# Laser_Tec_Control.net
KiCad netlist of a schematic drawn in Altium Designer
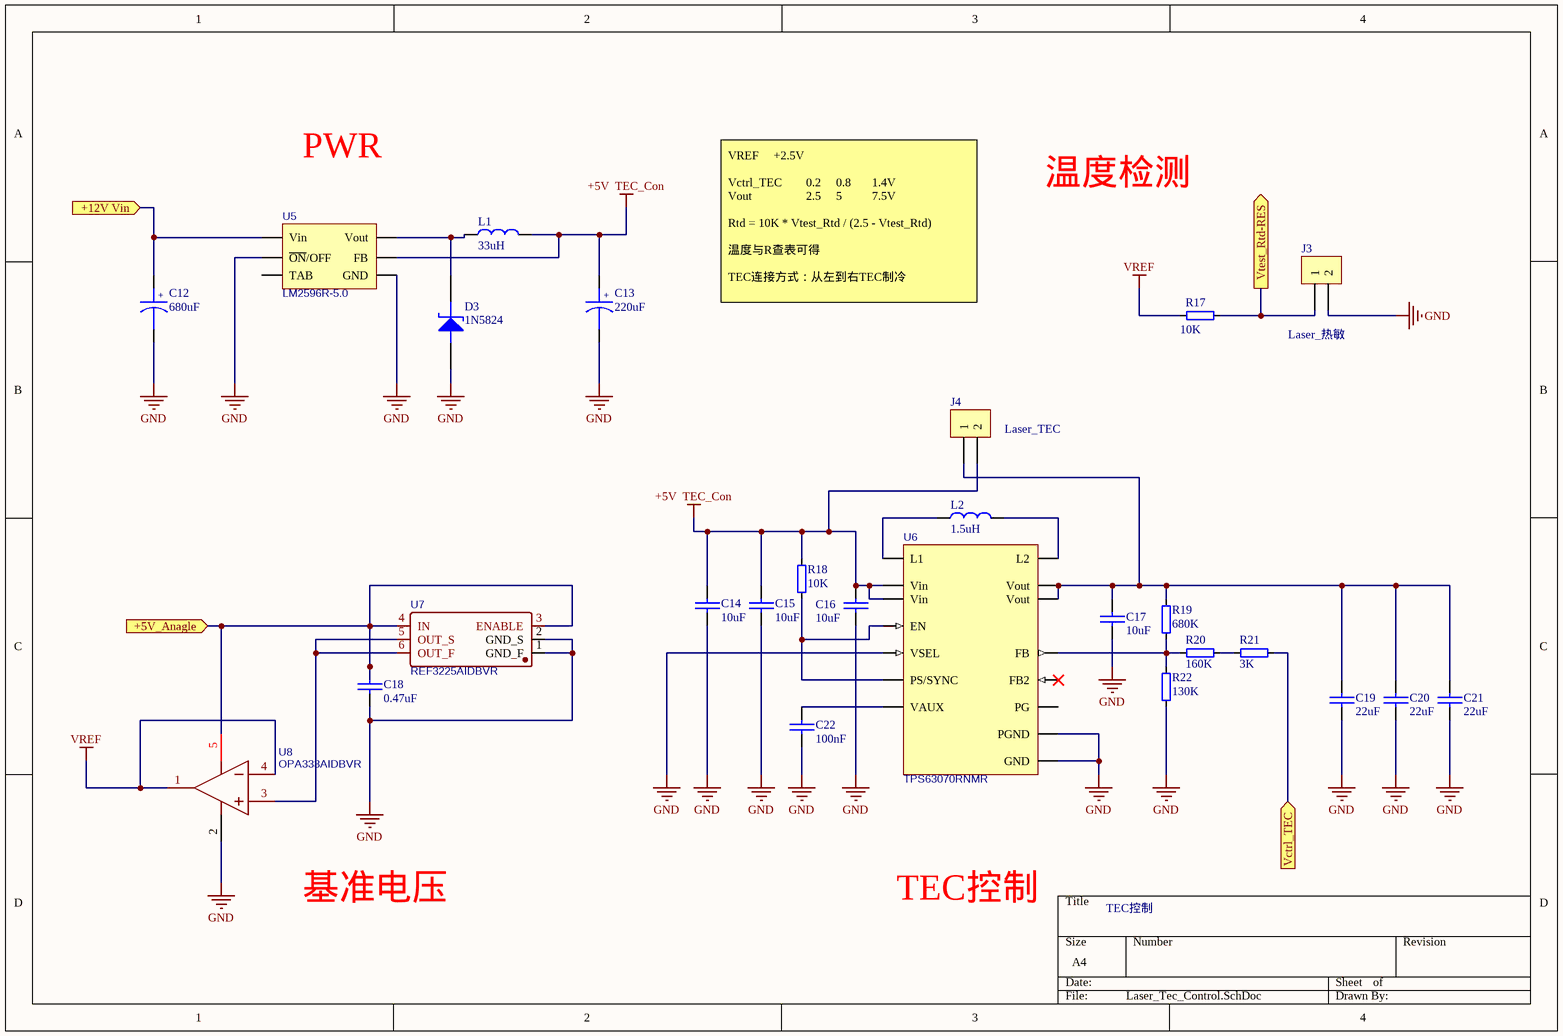
[diagram p0: Laser_Tec_Control.SchDoc]

(export (version "E")
  (design (tool "Eeschema 10.0.6"))
  (components
    (comp (ref "C12")
      (value "680uF")
      (footprint "CAP-TH_BD8.0-P3.50-D0.6-FD")
      (description "Capacitor")
      (libsource (lib "Laser Controller") (part "电解电容1"))
    )
    (comp (ref "C13")
      (value "220uF")
      (footprint "CAP-TH_BD8.0-P3.50-D0.6-FD")
      (description "Capacitor")
      (libsource (lib "Laser Controller") (part "电解电容1"))
    )
    (comp (ref "C14")
      (value "10uF")
      (footprint "C 0603_M")
      (description "Capacitor 0805")
      (libsource (lib "Laser Controller") (part "普通电容"))
    )
    (comp (ref "C15")
      (value "10uF")
      (footprint "C 0603_M")
      (description "Capacitor,0805")
      (libsource (lib "Laser Controller") (part "普通电容"))
    )
    (comp (ref "C16")
      (value "10uF")
      (footprint "C 0603_M")
      (description "Capacitor,0603")
      (libsource (lib "Laser Controller") (part "普通电容"))
    )
    (comp (ref "C17")
      (value "10uF")
      (footprint "C 0603_M")
      (description "Capacitor,0603")
      (libsource (lib "Laser Controller") (part "普通电容"))
    )
    (comp (ref "C18")
      (value "0.47uF")
      (footprint "C 0603_M")
      (description "Capacitor")
      (libsource (lib "Laser Controller") (part "普通电容"))
    )
    (comp (ref "C19")
      (value "22uF")
      (footprint "C 0603_M")
      (description "Capacitor,0805")
      (libsource (lib "Laser Controller") (part "普通电容"))
    )
    (comp (ref "C20")
      (value "22uF")
      (footprint "C 0603_M")
      (description "Capacitor 0805")
      (libsource (lib "Laser Controller") (part "普通电容"))
    )
    (comp (ref "C21")
      (value "22uF")
      (footprint "C 0603_M")
      (description "Capacitor 0805")
      (libsource (lib "Laser Controller") (part "普通电容"))
    )
    (comp (ref "C22")
      (value "100nF")
      (footprint "C 0603_M")
      (description "Capacitor")
      (libsource (lib "Laser Controller") (part "普通电容"))
    )
    (comp (ref "D3")
      (value "1N5824")
      (footprint "SMA_L4.3-W2.6-LS5.0-RD")
      (description "Zener Diode")
      (libsource (lib "Laser Controller") (part "1N5824"))
    )
    (comp (ref "J3")
      (value "Laser_热敏")
      (footprint "KF128-5.08-2P")
      (description "jointbar")
      (libsource (lib "Laser Controller") (part "SIP2"))
    )
    (comp (ref "J4")
      (value "Laser_TEC")
      (footprint "KF128-5.08-2P")
      (description "jointbar")
      (libsource (lib "Laser Controller") (part "SIP2"))
    )
    (comp (ref "L1")
      (value "33uH")
      (footprint "L 0805")
      (description "电感")
      (libsource (lib "Laser Controller") (part "L1"))
    )
    (comp (ref "L2")
      (value "1.5uH")
      (footprint "L 0805")
      (description "电感")
      (libsource (lib "Laser Controller") (part "L1"))
    )
    (comp (ref "R17") (value "10K") (footprint "0603R") (libsource (lib "Laser Controller") (part "普通电阻")))
    (comp (ref "R18") (value "10K") (footprint "0603R") (libsource (lib "Laser Controller") (part "普通电阻")))
    (comp (ref "R19") (value "680K") (footprint "0603R") (libsource (lib "Laser Controller") (part "普通电阻")))
    (comp (ref "R20") (value "160K") (footprint "0603R") (libsource (lib "Laser Controller") (part "普通电阻")))
    (comp (ref "R21") (value "3K") (footprint "0603R") (libsource (lib "Laser Controller") (part "普通电阻")))
    (comp (ref "R22") (value "130K") (footprint "0603R") (libsource (lib "Laser Controller") (part "普通电阻")))
    (comp (ref "U5")
      (value "LM2596R-5.0")
      (footprint "TO-263-5_L10.2-W8.6-P1.70-LS14.4-TL")
      (fields (field (name "BOM_SUPPLIER PART") "C77782"))
      (libsource (lib "Laser Controller") (part "LM2596R-5.0"))
    )
    (comp (ref "U6")
      (value "TPS63070RNMR")
      (footprint "VQFN-HR-15_L3.0-W2.5-P0.50-BL_TPS63070RNMR")
      (fields (field (name "BOM_SUPPLIER PART") "C109322"))
      (libsource (lib "Laser Controller") (part "TPS63070RNMR"))
    )
    (comp (ref "U7")
      (value "REF3225AIDBVR")
      (footprint "SOT-23-6_L2.9-W1.6-P0.95-LS2.8-BL")
      (fields (field (name "BOM_SUPPLIER PART") "C40852"))
      (libsource (lib "Laser Controller") (part "REF3225AIDBVR"))
    )
    (comp (ref "U8")
      (value "OPA333AIDBVR")
      (footprint "SOT-23-5_L3.0-W1.7-P0.95-LS2.8-BR")
      (fields (field (name "BOM_SUPPLIER PART") "C30878") (field (name "CONTRIBUTOR") "LCSC"))
      (libsource (lib "Laser Controller") (part "OPA333AIDBVR"))
    )
  )
  (nets
    (net (code "1") (name "+5V  TEC_Con") (class "Default")
      (node (ref "C13") (pin "1") (pinfunction "1_1") (pintype "passive"))
      (node (ref "C14") (pin "1") (pinfunction "1_1") (pintype "passive"))
      (node (ref "C15") (pin "1") (pinfunction "1_1") (pintype "passive"))
      (node (ref "C16") (pin "1") (pinfunction "1_1") (pintype "passive"))
      (node (ref "J4") (pin "2") (pinfunction "2_2") (pintype "passive"))
      (node (ref "L1") (pin "1") (pinfunction "1_1") (pintype "passive"))
      (node (ref "R18") (pin "2") (pinfunction "2_2") (pintype "passive"))
      (node (ref "U5") (pin "4") (pinfunction "FB_4") (pintype "passive"))
      (node (ref "U6") (pin "12") (pinfunction "Vin_12") (pintype "passive"))
      (node (ref "U6") (pin "13") (pinfunction "Vin_13") (pintype "passive"))
    )
    (net (code "2") (name "/+5V_Anagle") (class "Default")
      (node (ref "C18") (pin "1") (pinfunction "1_1") (pintype "passive"))
      (node (ref "U7") (pin "3") (pinfunction "ENABLE_3") (pintype "passive"))
      (node (ref "U7") (pin "4") (pinfunction "IN_4") (pintype "passive"))
      (node (ref "U8") (pin "5") (pinfunction "V+_5") (pintype "passive"))
    )
    (net (code "3") (name "/+12V Vin") (class "Default")
      (node (ref "C12") (pin "1") (pinfunction "1_1") (pintype "passive"))
      (node (ref "U5") (pin "1") (pinfunction "Vin_1") (pintype "passive"))
    )
    (net (code "4") (name "/Vctrl_TEC") (class "Default")
      (node (ref "R21") (pin "1") (pinfunction "1_1") (pintype "passive"))
    )
    (net (code "5") (name "/Vtest_Rtd-RES") (class "Default")
      (node (ref "J3") (pin "1") (pinfunction "1_1") (pintype "passive"))
      (node (ref "R17") (pin "2") (pinfunction "2_2") (pintype "passive"))
    )
    (net (code "6") (name "GND") (class "Default")
      (node (ref "C12") (pin "2") (pinfunction "2_2") (pintype "passive"))
      (node (ref "C13") (pin "2") (pinfunction "2_2") (pintype "passive"))
      (node (ref "C14") (pin "2") (pinfunction "2_2") (pintype "passive"))
      (node (ref "C15") (pin "2") (pinfunction "2_2") (pintype "passive"))
      (node (ref "C16") (pin "2") (pinfunction "2_2") (pintype "passive"))
      (node (ref "C17") (pin "2") (pinfunction "2_2") (pintype "passive"))
      (node (ref "C18") (pin "2") (pinfunction "2_2") (pintype "passive"))
      (node (ref "C19") (pin "2") (pinfunction "2_2") (pintype "passive"))
      (node (ref "C20") (pin "2") (pinfunction "2_2") (pintype "passive"))
      (node (ref "C21") (pin "2") (pinfunction "2_2") (pintype "passive"))
      (node (ref "C22") (pin "2") (pinfunction "2_2") (pintype "passive"))
      (node (ref "D3") (pin "1") (pinfunction "A_1") (pintype "passive"))
      (node (ref "J3") (pin "2") (pinfunction "2_2") (pintype "passive"))
      (node (ref "R22") (pin "1") (pinfunction "1_1") (pintype "passive"))
      (node (ref "U5") (pin "3") (pinfunction "GND_3") (pintype "passive"))
      (node (ref "U5") (pin "5") (pinfunction "~{ON}/OFF_5") (pintype "passive"))
      (node (ref "U6") (pin "10") (pinfunction "PGND_10") (pintype "passive"))
      (node (ref "U6") (pin "15") (pinfunction "VSEL_15") (pintype "input"))
      (node (ref "U6") (pin "4") (pinfunction "GND_4") (pintype "passive"))
      (node (ref "U7") (pin "1") (pinfunction "GND_F_1") (pintype "passive"))
      (node (ref "U7") (pin "2") (pinfunction "GND_S_2") (pintype "passive"))
      (node (ref "U8") (pin "2") (pinfunction "V-_2") (pintype "passive"))
    )
    (net (code "7") (name "Net-(C17-Pad1)") (class "Default")
      (node (ref "C17") (pin "1") (pinfunction "1_1") (pintype "passive"))
      (node (ref "C19") (pin "1") (pinfunction "1_1") (pintype "passive"))
      (node (ref "C20") (pin "1") (pinfunction "1_1") (pintype "passive"))
      (node (ref "C21") (pin "1") (pinfunction "1_1") (pintype "passive"))
      (node (ref "J4") (pin "1") (pinfunction "1_1") (pintype "passive"))
      (node (ref "R19") (pin "2") (pinfunction "2_2") (pintype "passive"))
      (node (ref "U6") (pin "7") (pinfunction "Vout_7") (pintype "passive"))
      (node (ref "U6") (pin "8") (pinfunction "Vout_8") (pintype "passive"))
    )
    (net (code "8") (name "Net-(D3-K)") (class "Default")
      (node (ref "D3") (pin "2") (pinfunction "K_2") (pintype "passive"))
      (node (ref "L1") (pin "2") (pinfunction "2_2") (pintype "passive"))
      (node (ref "U5") (pin "2") (pinfunction "Vout_2") (pintype "passive"))
    )
    (net (code "9") (name "Net-(R20-Pad1)") (class "Default")
      (node (ref "R20") (pin "1") (pinfunction "1_1") (pintype "passive"))
      (node (ref "R21") (pin "2") (pinfunction "2_2") (pintype "passive"))
    )
    (net (code "10") (name "Net-(U6-EN)") (class "Default")
      (node (ref "R18") (pin "1") (pinfunction "1_1") (pintype "passive"))
      (node (ref "U6") (pin "1") (pinfunction "PS/SYNC_1") (pintype "passive"))
      (node (ref "U6") (pin "14") (pinfunction "EN_14") (pintype "input"))
    )
    (net (code "11") (name "Net-(U6-FB)") (class "Default")
      (node (ref "R19") (pin "1") (pinfunction "1_1") (pintype "passive"))
      (node (ref "R20") (pin "2") (pinfunction "2_2") (pintype "passive"))
      (node (ref "R22") (pin "2") (pinfunction "2_2") (pintype "passive"))
      (node (ref "U6") (pin "5") (pinfunction "FB_5") (pintype "output"))
    )
    (net (code "12") (name "Net-(U6-L1)") (class "Default")
      (node (ref "L2") (pin "2") (pinfunction "2_2") (pintype "passive"))
      (node (ref "U6") (pin "11") (pinfunction "L1_11") (pintype "passive"))
    )
    (net (code "13") (name "Net-(U6-L2)") (class "Default")
      (node (ref "L2") (pin "1") (pinfunction "1_1") (pintype "passive"))
      (node (ref "U6") (pin "9") (pinfunction "L2_9") (pintype "passive"))
    )
    (net (code "14") (name "Net-(U6-VAUX)") (class "Default")
      (node (ref "C22") (pin "1") (pinfunction "1_1") (pintype "passive"))
      (node (ref "U6") (pin "3") (pinfunction "VAUX_3") (pintype "passive"))
    )
    (net (code "15") (name "Net-(U7-OUT_F)") (class "Default")
      (node (ref "U7") (pin "5") (pinfunction "OUT_S_5") (pintype "passive"))
      (node (ref "U7") (pin "6") (pinfunction "OUT_F_6") (pintype "passive"))
      (node (ref "U8") (pin "3") (pinfunction "IN+_3") (pintype "passive"))
    )
    (net (code "16") (name "VREF") (class "Default")
      (node (ref "R17") (pin "1") (pinfunction "1_1") (pintype "passive"))
      (node (ref "U8") (pin "1") (pinfunction "OUT_1") (pintype "passive"))
      (node (ref "U8") (pin "4") (pinfunction "IN-_4") (pintype "passive"))
    )
    (net (code "17") (name "unconnected-(U5-TAB-Pad6)") (class "Default")
      (node (ref "U5") (pin "6") (pinfunction "TAB_6") (pintype "passive"))
    )
    (net (code "18") (name "unconnected-(U6-FB2-Pad6)") (class "Default")
      (node (ref "U6") (pin "6") (pinfunction "FB2_6") (pintype "input+no_connect"))
    )
    (net (code "19") (name "unconnected-(U6-PG-Pad2)") (class "Default")
      (node (ref "U6") (pin "2") (pinfunction "PG_2") (pintype "passive"))
    )
  )
)
